# S03-BEAGLEBONE.net
KiCad netlist of a schematic drawn in Altium Designer
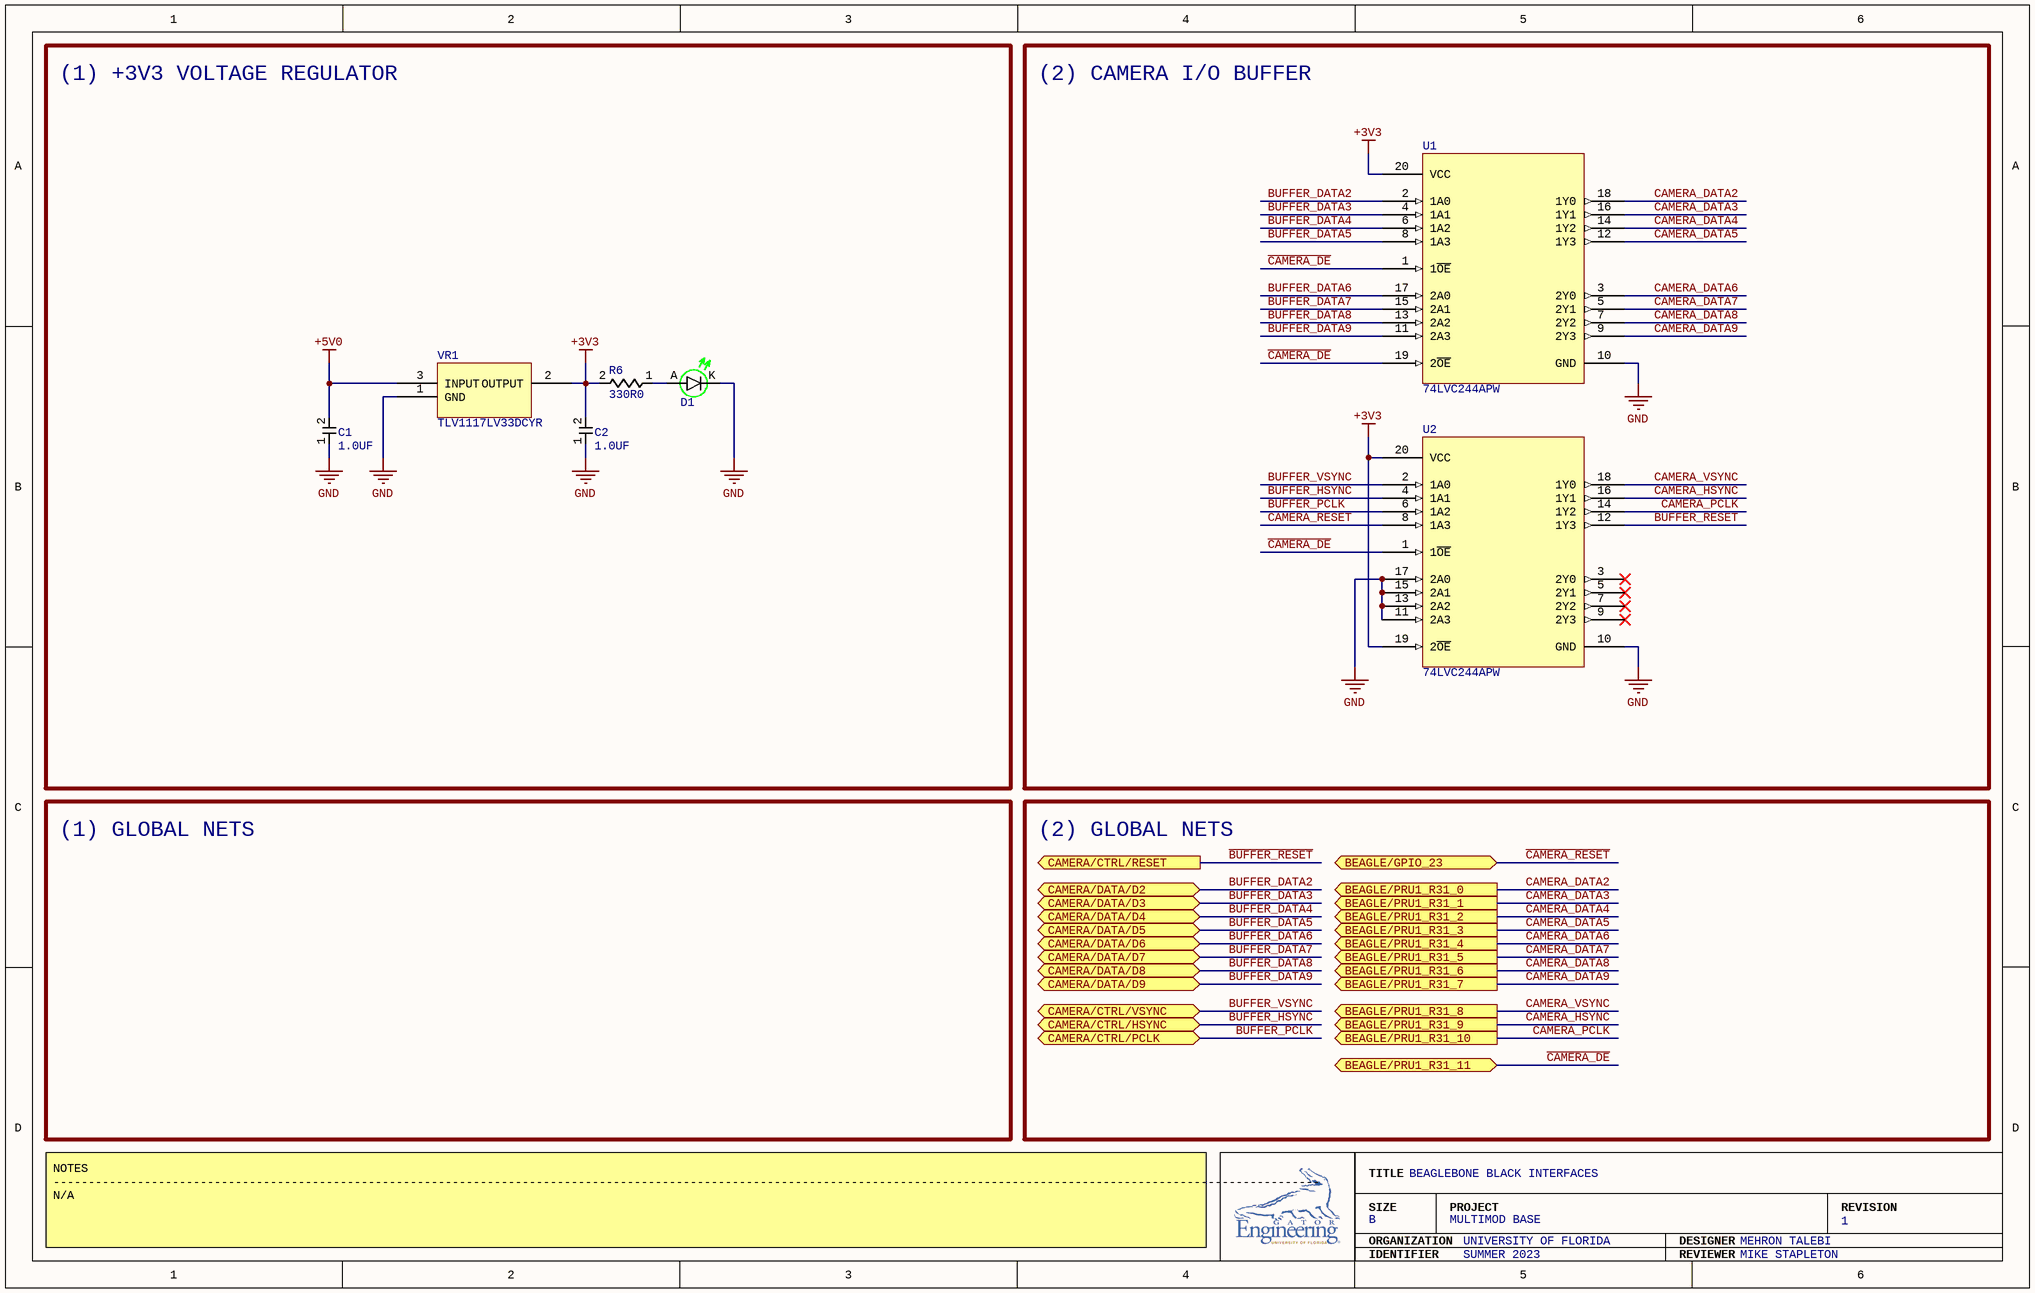
[diagram p0: S03-BEAGLEBONE.SchDoc]

(export (version "E")
  (design (tool "Eeschema 10.0.6"))
  (components
    (comp (ref "C1")
      (value "1.0UF")
      (footprint "CL21B105KAFNFNE")
      (description "CAP CER 1UF 25V X7R 0805")
      (fields (field (name "TOLERANCE") "±10%"))
      (libsource (lib "Master") (part "CL21B105KAFNFNE"))
    )
    (comp (ref "C2")
      (value "1.0UF")
      (footprint "CL21B105KAFNFNE")
      (description "CAP CER 1UF 25V X7R 0805")
      (fields (field (name "TOLERANCE") "±10%"))
      (libsource (lib "Master") (part "CL21B105KAFNFNE"))
    )
    (comp (ref "D1")
      (value "LTST-C171GKT")
      (footprint "LTST-C171GKT")
      (description "LED GREEN CLEAR CHIP SMD")
      (libsource (lib "Master") (part "LTST-C171GKT"))
    )
    (comp (ref "R6")
      (value "330R0")
      (footprint "RC0805FR-7W330RL")
      (description "RES 330 OHM 1% 1/4W 0805")
      (fields (field (name "TOLERANCE") "±1%"))
      (libsource (lib "Master") (part "RC0805FR-7W330RL"))
    )
    (comp (ref "U1")
      (value "74LVC244APW")
      (footprint "74LVC244APW")
      (description "IC BUF NON-INVERT 3.6V 20TSSOP")
      (libsource (lib "Master") (part "74LVC244APW"))
    )
    (comp (ref "U2")
      (value "74LVC244APW")
      (footprint "74LVC244APW")
      (description "IC BUF NON-INVERT 3.6V 20TSSOP")
      (libsource (lib "Master") (part "74LVC244APW"))
    )
    (comp (ref "VR1")
      (value "TLV1117LV33DCYR")
      (footprint "TLV1117LV33DCYR")
      (description "IC REG LINEAR 3.3V 1A SOT223-4")
      (libsource (lib "Master") (part "TLV1117LV33DCYR"))
    )
  )
  (nets
    (net (code "1") (name "+3V3") (class "Default")
      (node (ref "C2") (pin "2") (pinfunction "2_2") (pintype "passive"))
      (node (ref "R6") (pin "2") (pinfunction "2_2") (pintype "passive"))
      (node (ref "U1") (pin "20") (pinfunction "VCC_20") (pintype "power_in"))
      (node (ref "U2") (pin "19") (pinfunction "2~{OE}_19") (pintype "input"))
      (node (ref "U2") (pin "20") (pinfunction "VCC_20") (pintype "power_in"))
      (node (ref "VR1") (pin "2") (pinfunction "OUTPUT_2") (pintype "passive"))
    )
    (net (code "2") (name "+5V0") (class "Default")
      (node (ref "C1") (pin "2") (pinfunction "2_2") (pintype "passive"))
      (node (ref "VR1") (pin "3") (pinfunction "INPUT_3") (pintype "passive"))
    )
    (net (code "3") (name "/BUFFER_DATA2") (class "Default")
      (node (ref "U1") (pin "2") (pinfunction "1A0_2") (pintype "input"))
    )
    (net (code "4") (name "/BUFFER_DATA3") (class "Default")
      (node (ref "U1") (pin "4") (pinfunction "1A1_4") (pintype "input"))
    )
    (net (code "5") (name "/BUFFER_DATA4") (class "Default")
      (node (ref "U1") (pin "6") (pinfunction "1A2_6") (pintype "input"))
    )
    (net (code "6") (name "/BUFFER_DATA5") (class "Default")
      (node (ref "U1") (pin "8") (pinfunction "1A3_8") (pintype "input"))
    )
    (net (code "7") (name "/BUFFER_DATA6") (class "Default")
      (node (ref "U1") (pin "17") (pinfunction "2A0_17") (pintype "input"))
    )
    (net (code "8") (name "/BUFFER_DATA7") (class "Default")
      (node (ref "U1") (pin "15") (pinfunction "2A1_15") (pintype "input"))
    )
    (net (code "9") (name "/BUFFER_DATA8") (class "Default")
      (node (ref "U1") (pin "13") (pinfunction "2A2_13") (pintype "input"))
    )
    (net (code "10") (name "/BUFFER_DATA9") (class "Default")
      (node (ref "U1") (pin "11") (pinfunction "2A3_11") (pintype "input"))
    )
    (net (code "11") (name "/BUFFER_HSYNC") (class "Default")
      (node (ref "U2") (pin "4") (pinfunction "1A1_4") (pintype "input"))
    )
    (net (code "12") (name "/BUFFER_PCLK") (class "Default")
      (node (ref "U2") (pin "6") (pinfunction "1A2_6") (pintype "input"))
    )
    (net (code "13") (name "/BUFFER_RESET") (class "Default")
      (node (ref "U2") (pin "12") (pinfunction "1Y3_12") (pintype "output"))
    )
    (net (code "14") (name "/BUFFER_VSYNC") (class "Default")
      (node (ref "U2") (pin "2") (pinfunction "1A0_2") (pintype "input"))
    )
    (net (code "15") (name "/CAMERA_DATA2") (class "Default")
      (node (ref "U1") (pin "18") (pinfunction "1Y0_18") (pintype "output"))
    )
    (net (code "16") (name "/CAMERA_DATA3") (class "Default")
      (node (ref "U1") (pin "16") (pinfunction "1Y1_16") (pintype "output"))
    )
    (net (code "17") (name "/CAMERA_DATA4") (class "Default")
      (node (ref "U1") (pin "14") (pinfunction "1Y2_14") (pintype "output"))
    )
    (net (code "18") (name "/CAMERA_DATA5") (class "Default")
      (node (ref "U1") (pin "12") (pinfunction "1Y3_12") (pintype "output"))
    )
    (net (code "19") (name "/CAMERA_DATA6") (class "Default")
      (node (ref "U1") (pin "3") (pinfunction "2Y0_3") (pintype "output"))
    )
    (net (code "20") (name "/CAMERA_DATA7") (class "Default")
      (node (ref "U1") (pin "5") (pinfunction "2Y1_5") (pintype "output"))
    )
    (net (code "21") (name "/CAMERA_DATA8") (class "Default")
      (node (ref "U1") (pin "7") (pinfunction "2Y2_7") (pintype "output"))
    )
    (net (code "22") (name "/CAMERA_DATA9") (class "Default")
      (node (ref "U1") (pin "9") (pinfunction "2Y3_9") (pintype "output"))
    )
    (net (code "23") (name "/CAMERA_DE") (class "Default")
      (node (ref "U1") (pin "1") (pinfunction "1~{OE}_1") (pintype "input"))
      (node (ref "U1") (pin "19") (pinfunction "2~{OE}_19") (pintype "input"))
      (node (ref "U2") (pin "1") (pinfunction "1~{OE}_1") (pintype "input"))
    )
    (net (code "24") (name "/CAMERA_HSYNC") (class "Default")
      (node (ref "U2") (pin "16") (pinfunction "1Y1_16") (pintype "output"))
    )
    (net (code "25") (name "/CAMERA_PCLK") (class "Default")
      (node (ref "U2") (pin "14") (pinfunction "1Y2_14") (pintype "output"))
    )
    (net (code "26") (name "/CAMERA_RESET") (class "Default")
      (node (ref "U2") (pin "8") (pinfunction "1A3_8") (pintype "input"))
    )
    (net (code "27") (name "/CAMERA_VSYNC") (class "Default")
      (node (ref "U2") (pin "18") (pinfunction "1Y0_18") (pintype "output"))
    )
    (net (code "28") (name "GND") (class "Default")
      (node (ref "C1") (pin "1") (pinfunction "1_1") (pintype "passive"))
      (node (ref "C2") (pin "1") (pinfunction "1_1") (pintype "passive"))
      (node (ref "D1") (pin "K") (pinfunction "K_K") (pintype "passive"))
      (node (ref "U1") (pin "10") (pinfunction "GND_10") (pintype "power_in"))
      (node (ref "U2") (pin "10") (pinfunction "GND_10") (pintype "power_in"))
      (node (ref "U2") (pin "11") (pinfunction "2A3_11") (pintype "input"))
      (node (ref "U2") (pin "13") (pinfunction "2A2_13") (pintype "input"))
      (node (ref "U2") (pin "15") (pinfunction "2A1_15") (pintype "input"))
      (node (ref "U2") (pin "17") (pinfunction "2A0_17") (pintype "input"))
      (node (ref "VR1") (pin "1") (pinfunction "GND_1") (pintype "passive"))
    )
    (net (code "29") (name "Net-(D1-PadA)") (class "Default")
      (node (ref "D1") (pin "A") (pinfunction "A_A") (pintype "passive"))
      (node (ref "R6") (pin "1") (pinfunction "1_1") (pintype "passive"))
    )
    (net (code "30") (name "unconnected-(U2-2Y0-Pad3)") (class "Default")
      (node (ref "U2") (pin "3") (pinfunction "2Y0_3") (pintype "output+no_connect"))
    )
    (net (code "31") (name "unconnected-(U2-2Y1-Pad5)") (class "Default")
      (node (ref "U2") (pin "5") (pinfunction "2Y1_5") (pintype "output+no_connect"))
    )
    (net (code "32") (name "unconnected-(U2-2Y2-Pad7)") (class "Default")
      (node (ref "U2") (pin "7") (pinfunction "2Y2_7") (pintype "output+no_connect"))
    )
    (net (code "33") (name "unconnected-(U2-2Y3-Pad9)") (class "Default")
      (node (ref "U2") (pin "9") (pinfunction "2Y3_9") (pintype "output+no_connect"))
    )
  )
)
